# amp.net
KiCad netlist of a schematic drawn in Altium Designer
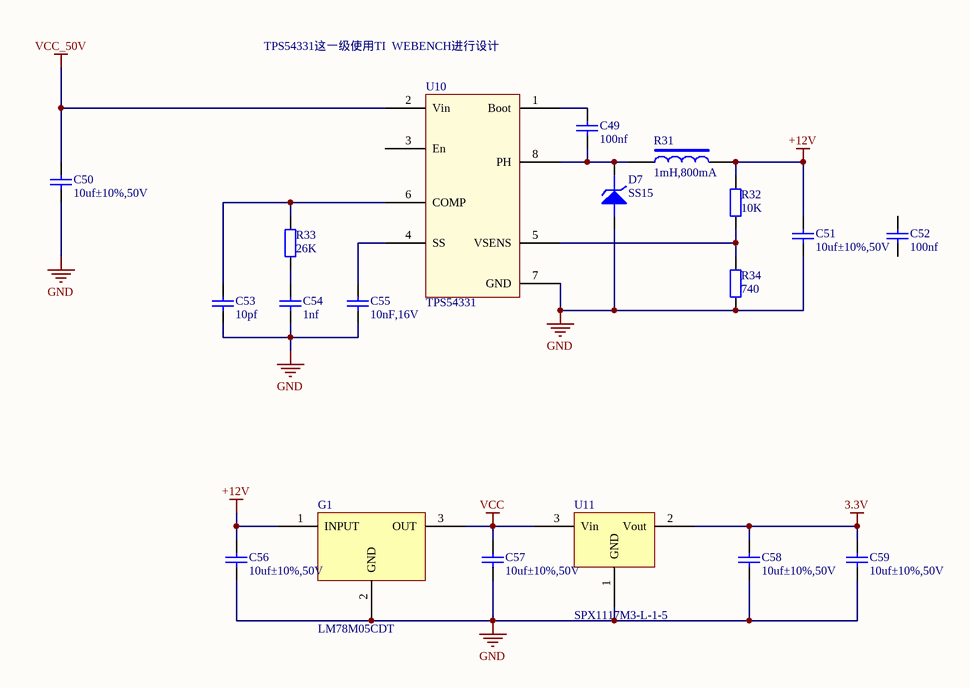
[diagram p0: amp.SchDoc]

(export (version "E")
  (design (tool "Eeschema 10.0.6"))
  (components
    (comp (ref "C49")
      (value "100nf")
      (footprint "0603")
      (description "贴片电容")
      (libsource (lib "Capacitor  V1.00") (part "贴片电容,0603,10nF±10%,16V"))
    )
    (comp (ref "C50")
      (value "10uf±10%,50V")
      (footprint "1206")
      (description "贴片电容")
      (libsource (lib "Capacitor  V1.00") (part "贴片电容,1206,10uf±10%,50V"))
    )
    (comp (ref "C51")
      (value "10uf±10%,50V")
      (footprint "1206")
      (description "贴片电容")
      (libsource (lib "Capacitor  V1.00") (part "贴片电容,1206,10uf±10%,50V"))
    )
    (comp (ref "C52")
      (value "100nf")
      (footprint "0603")
      (description "贴片电容")
      (libsource (lib "Capacitor  V1.00") (part "贴片电容,0603,10nF±10%,16V"))
    )
    (comp (ref "C53")
      (value "10pf")
      (footprint "0603")
      (description "贴片电容")
      (libsource (lib "Capacitor  V1.00") (part "贴片电容,0603,10nF±10%,16V"))
    )
    (comp (ref "C54")
      (value "1nf")
      (footprint "0603")
      (description "贴片电容")
      (libsource (lib "Capacitor  V1.00") (part "贴片电容,0603,10nF±10%,16V"))
    )
    (comp (ref "C55")
      (value "10nF,16V")
      (footprint "0603")
      (description "贴片电容")
      (libsource (lib "Capacitor  V1.00") (part "贴片电容,0603,10nF±10%,16V"))
    )
    (comp (ref "C56")
      (value "10uf±10%,50V")
      (footprint "1206")
      (description "贴片电容")
      (libsource (lib "Capacitor  V1.00") (part "贴片电容,1206,10uf±10%,50V"))
    )
    (comp (ref "C57")
      (value "10uf±10%,50V")
      (footprint "1206")
      (description "贴片电容")
      (libsource (lib "Capacitor  V1.00") (part "贴片电容,1206,10uf±10%,50V"))
    )
    (comp (ref "C58")
      (value "10uf±10%,50V")
      (footprint "1206")
      (description "贴片电容")
      (libsource (lib "Capacitor  V1.00") (part "贴片电容,1206,10uf±10%,50V"))
    )
    (comp (ref "C59")
      (value "10uf±10%,50V")
      (footprint "1206")
      (description "贴片电容")
      (libsource (lib "Capacitor  V1.00") (part "贴片电容,1206,10uf±10%,50V"))
    )
    (comp (ref "D7")
      (value "SS15")
      (footprint "SMA")
      (description "肖特基二极管")
      (libsource (lib "Diodes&Mosfets V1.00") (part "肖特基二极管,SS15,50V,1A,SMA"))
    )
    (comp (ref "G1")
      (value "LM78M05CDT")
      (footprint "TO-252")
      (description "电压转换器")
      (libsource (lib "Integrated chip V1.00") (part "电压转换器,LM78M05CDT,TO-252"))
    )
    (comp (ref "R31")
      (value "1mH,800mA")
      (footprint "0603_induct")
      (description "贴片电感")
      (libsource (lib "电磁性元件  V1.00") (part "1mH,800mA,0810"))
    )
    (comp (ref "R32")
      (value "10K")
      (footprint "0603")
      (description "贴片电阻")
      (libsource (lib "Resistor  V1.00") (part "6.2K±1%,1/10W,0603"))
    )
    (comp (ref "R33")
      (value "26K")
      (footprint "0603")
      (description "贴片电阻")
      (libsource (lib "Resistor  V1.00") (part "6.2K±1%,1/10W,0603"))
    )
    (comp (ref "R34")
      (value "740")
      (footprint "0603")
      (description "贴片电阻")
      (libsource (lib "Resistor  V1.00") (part "6.2K±1%,1/10W,0603"))
    )
    (comp (ref "U10")
      (value "TPS54331")
      (footprint "SOIC-8")
      (libsource (lib "buck_boost") (part "TPS54331-sop8"))
    )
    (comp (ref "U11")
      (value "SPX1117M3-L-1-5")
      (footprint "SOT-223")
      (description "电压转换器")
      (libsource (lib "Integrated chip V1.00") (part "电压转换器,SPX1117M3-L-1-5,SOT-223,环保"))
    )
  )
  (nets
    (net (code "1") (name "+12V") (class "Default")
      (node (ref "C51") (pin "2") (pinfunction "2_2") (pintype "passive"))
      (node (ref "C56") (pin "2") (pinfunction "2_2") (pintype "passive"))
      (node (ref "G1") (pin "1") (pinfunction "INPUT_1") (pintype "passive"))
      (node (ref "R31") (pin "2") (pinfunction "2_2") (pintype "passive"))
      (node (ref "R32") (pin "2") (pinfunction "2_2") (pintype "passive"))
    )
    (net (code "2") (name "3.3V") (class "Default")
      (node (ref "C58") (pin "2") (pinfunction "2_2") (pintype "passive"))
      (node (ref "C59") (pin "2") (pinfunction "2_2") (pintype "passive"))
      (node (ref "U11") (pin "2") (pinfunction "Vout_2") (pintype "passive"))
    )
    (net (code "3") (name "GND") (class "Default")
      (node (ref "C50") (pin "1") (pinfunction "1_1") (pintype "passive"))
      (node (ref "C51") (pin "1") (pinfunction "1_1") (pintype "passive"))
      (node (ref "C53") (pin "1") (pinfunction "1_1") (pintype "passive"))
      (node (ref "C54") (pin "1") (pinfunction "1_1") (pintype "passive"))
      (node (ref "C55") (pin "1") (pinfunction "1_1") (pintype "passive"))
      (node (ref "C56") (pin "1") (pinfunction "1_1") (pintype "passive"))
      (node (ref "C57") (pin "1") (pinfunction "1_1") (pintype "passive"))
      (node (ref "C58") (pin "1") (pinfunction "1_1") (pintype "passive"))
      (node (ref "C59") (pin "1") (pinfunction "1_1") (pintype "passive"))
      (node (ref "D7") (pin "1") (pinfunction "A_1") (pintype "passive"))
      (node (ref "G1") (pin "2") (pinfunction "GND_2") (pintype "passive"))
      (node (ref "R34") (pin "1") (pinfunction "1_1") (pintype "passive"))
      (node (ref "U10") (pin "7") (pinfunction "GND_7") (pintype "passive"))
      (node (ref "U11") (pin "1") (pinfunction "GND_1") (pintype "passive"))
    )
    (net (code "4") (name "Net-(C54-Pad2)") (class "Default")
      (node (ref "C54") (pin "2") (pinfunction "2_2") (pintype "passive"))
      (node (ref "R33") (pin "1") (pinfunction "1_1") (pintype "passive"))
    )
    (net (code "5") (name "Net-(D7-K)") (class "Default")
      (node (ref "C49") (pin "1") (pinfunction "1_1") (pintype "passive"))
      (node (ref "D7") (pin "2") (pinfunction "K_2") (pintype "passive"))
      (node (ref "R31") (pin "1") (pinfunction "1_1") (pintype "passive"))
      (node (ref "U10") (pin "8") (pinfunction "PH_8") (pintype "passive"))
    )
    (net (code "6") (name "Net-(U10-Boot)") (class "Default")
      (node (ref "C49") (pin "2") (pinfunction "2_2") (pintype "passive"))
      (node (ref "U10") (pin "1") (pinfunction "Boot_1") (pintype "passive"))
    )
    (net (code "7") (name "Net-(U10-COMP)") (class "Default")
      (node (ref "C53") (pin "2") (pinfunction "2_2") (pintype "passive"))
      (node (ref "R33") (pin "2") (pinfunction "2_2") (pintype "passive"))
      (node (ref "U10") (pin "6") (pinfunction "COMP_6") (pintype "passive"))
    )
    (net (code "8") (name "Net-(U10-SS)") (class "Default")
      (node (ref "C55") (pin "2") (pinfunction "2_2") (pintype "passive"))
      (node (ref "U10") (pin "4") (pinfunction "SS_4") (pintype "passive"))
    )
    (net (code "9") (name "Net-(U10-VSENS)") (class "Default")
      (node (ref "R32") (pin "1") (pinfunction "1_1") (pintype "passive"))
      (node (ref "R34") (pin "2") (pinfunction "2_2") (pintype "passive"))
      (node (ref "U10") (pin "5") (pinfunction "VSENS_5") (pintype "passive"))
    )
    (net (code "10") (name "VCC") (class "Default")
      (node (ref "C57") (pin "2") (pinfunction "2_2") (pintype "passive"))
      (node (ref "G1") (pin "3") (pinfunction "OUT_3") (pintype "passive"))
      (node (ref "U11") (pin "3") (pinfunction "Vin_3") (pintype "passive"))
    )
    (net (code "11") (name "VCC_50V") (class "Default")
      (node (ref "C50") (pin "2") (pinfunction "2_2") (pintype "passive"))
      (node (ref "U10") (pin "2") (pinfunction "Vin_2") (pintype "passive"))
    )
    (net (code "12") (name "unconnected-(C52-Pad1)") (class "Default")
      (node (ref "C52") (pin "1") (pinfunction "1_1") (pintype "passive"))
    )
    (net (code "13") (name "unconnected-(C52-Pad2)") (class "Default")
      (node (ref "C52") (pin "2") (pinfunction "2_2") (pintype "passive"))
    )
    (net (code "14") (name "unconnected-(U10-En-Pad3)") (class "Default")
      (node (ref "U10") (pin "3") (pinfunction "En_3") (pintype "passive"))
    )
  )
)
